# 07-POWER.net
KiCad netlist of a schematic drawn in Altium Designer
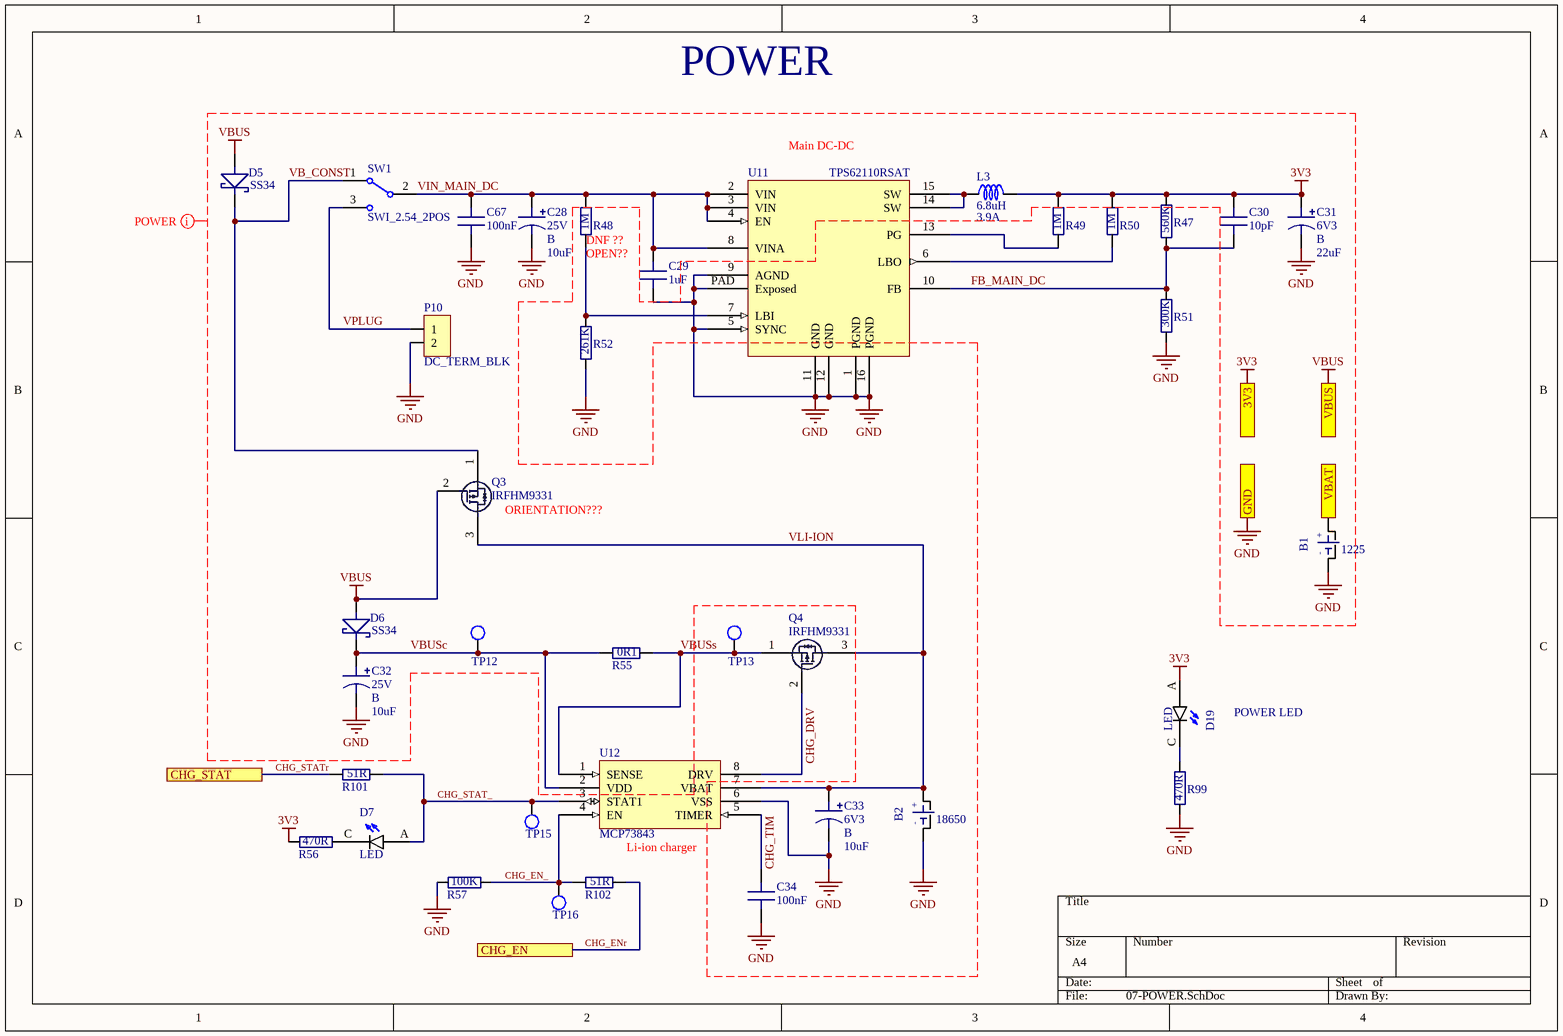
[diagram p0: 07-POWER.SchDoc]

(export (version "E")
  (design (tool "Eeschema 10.0.6"))
  (components
    (comp (ref "B1")
      (value "CR12XX_BH500")
      (footprint "BH500-CR1216/20/25-COMB")
      (description "Coin Cell Battery 3V 12 X 2.5 mm 48mA Holder")
      (fields
        (field (name "MP") "BR1225")
        (field (name "MF") "Panasonic Battery")
        (field (name "SIZE") "1225")
      )
      (libsource (lib "A.Shelestov_Batteries") (part "CR12XX_BH500"))
    )
    (comp (ref "B2")
      (value "18650_KEYS1042_HOLDER")
      (footprint "18650-COMBI")
      (description "18650 Li-ion Battery Holder")
      (fields (field (name "SIZE") "18650"))
      (libsource (lib "A.Shelestov_Batteries") (part "18650_KEYS1042_HOLDER"))
    )
    (comp (ref "C28")
      (value "10uF")
      (footprint "CAP_SIZE_B")
      (description "Tantalum capacitor")
      (fields (field (name "VOLTAGE") "25V") (field (name "SIZE") "B"))
      (libsource (lib "A.Shelestov_Capacitors") (part "CAP_B_10uF_25V"))
    )
    (comp (ref "C29")
      (value "1uF")
      (footprint "C0805")
      (description "Ceramic capacitor")
      (fields (field (name "VOLTAGE") "25V"))
      (libsource (lib "A.Shelestov_Capacitors") (part "C0805_1uF_25V"))
    )
    (comp (ref "C30")
      (value "10pF")
      (footprint "C0603")
      (description "Ceramic capacitor")
      (fields (field (name "VOLTAGE") "25V"))
      (libsource (lib "A.Shelestov_Capacitors") (part "C0603_10pF_25V"))
    )
    (comp (ref "C31")
      (value "22uF")
      (footprint "CAP_SIZE_B")
      (description "Tantalum capacitor")
      (fields (field (name "VOLTAGE") "6V3") (field (name "SIZE") "B"))
      (libsource (lib "A.Shelestov_Capacitors") (part "CAP_B_22uF_6V3"))
    )
    (comp (ref "C32")
      (value "10uF")
      (footprint "CAP_SIZE_B")
      (description "Tantalum capacitor")
      (fields (field (name "VOLTAGE") "25V") (field (name "SIZE") "B"))
      (libsource (lib "A.Shelestov_Capacitors") (part "CAP_B_10uF_25V"))
    )
    (comp (ref "C33")
      (value "10uF")
      (footprint "CAP_SIZE_B")
      (description "Tantalum capacitor")
      (fields (field (name "VOLTAGE") "6V3") (field (name "SIZE") "B"))
      (libsource (lib "A.Shelestov_Capacitors") (part "CAP_B_10uF_6V3"))
    )
    (comp (ref "C34")
      (value "100nF")
      (footprint "C0805")
      (description "Ceramic capacitor")
      (fields (field (name "VOLTAGE") "25V"))
      (libsource (lib "A.Shelestov_Capacitors") (part "C0805_100nF_25V"))
    )
    (comp (ref "C67")
      (value "100nF")
      (footprint "C0805")
      (description "Ceramic capacitor")
      (fields (field (name "VOLTAGE") "25V"))
      (libsource (lib "A.Shelestov_Capacitors") (part "C0805_100nF_25V"))
    )
    (comp (ref "D5")
      (value "SMD-DIODE-SCHOTTKY-40V-3A(DO-214AB)")
      (footprint "DO-214AC")
      (description "Rectifier, Schottky; DO-214AB; 3.0A IF; 0.75V; 40V; 100A IFRM; 10000V/us; 1000pF")
      (fields (field (name "MF") "Vishay") (field (name "MP") "SS34-E3/57T") (field (name "NAME") "SS34"))
      (libsource (lib "ComponentsLib") (part "D_SS-34"))
    )
    (comp (ref "D6")
      (value "SMD-DIODE-SCHOTTKY-40V-3A(DO-214AB)")
      (footprint "DO-214AC")
      (description "Rectifier, Schottky; DO-214AB; 3.0A IF; 0.75V; 40V; 100A IFRM; 10000V/us; 1000pF")
      (fields (field (name "MF") "Vishay") (field (name "MP") "SS34-E3/57T") (field (name "NAME") "SS34"))
      (libsource (lib "ComponentsLib") (part "D_SS-34"))
    )
    (comp (ref "D7")
      (value "LED")
      (footprint "LED_0604")
      (description "Led General")
      (fields (field (name "MF") "Dialight") (field (name "MP") "598-8140-107F"))
      (libsource (lib "ComponentsLib") (part "LED"))
    )
    (comp (ref "D19")
      (value "LED")
      (footprint "LED_0604")
      (description "Led General")
      (fields (field (name "MF") "Dialight") (field (name "MP") "598-8140-107F"))
      (libsource (lib "ComponentsLib") (part "LED"))
    )
    (comp (ref "L3")
      (value "*")
      (footprint "L_CDRH8D43")
      (description "Inductor Generic")
      (fields (field (name "CURRENT") "3.9A") (field (name "INDUCTIVITY") "6.8uH"))
      (libsource (lib "A.Shelestov_Inductors") (part "L_CDHR8D43_6.8uH_3.9A"))
    )
    (comp (ref "P10")
      (value "DC_TERM_BLK")
      (footprint "TERM_BLK_2.54")
      (libsource (lib "ComponentsLib") (part "DC_TERM_BLK"))
    )
    (comp (ref "Q3")
      (value "IRFHM9331")
      (footprint "PQFN-3x3")
      (description "-30V Single P-Channel HEXFET Power MOSFET in a PQFN 3mm x 3mm package")
      (libsource (lib "ComponentsLib") (part "IRFHM9331"))
    )
    (comp (ref "Q4")
      (value "IRFHM9331")
      (footprint "PQFN-3x3")
      (description "-30V Single P-Channel HEXFET Power MOSFET in a PQFN 3mm x 3mm package")
      (libsource (lib "ComponentsLib") (part "IRFHM9331"))
    )
    (comp (ref "R47")
      (value "~")
      (footprint "R0805")
      (description "Resistor General")
      (fields (field (name "TOLERANCE") "1%") (field (name "RESISTANCE") "560K"))
      (libsource (lib "A.Shelestov_Resistors") (part "R0805_560K_1%"))
    )
    (comp (ref "R48")
      (value "~")
      (footprint "R0805")
      (description "Resistor General")
      (fields (field (name "TOLERANCE") "1%") (field (name "RESISTANCE") "1M"))
      (libsource (lib "A.Shelestov_Resistors") (part "R0805_1M_1%"))
    )
    (comp (ref "R49")
      (value "~")
      (footprint "R0805")
      (description "Resistor General")
      (fields (field (name "TOLERANCE") "1%") (field (name "RESISTANCE") "1M"))
      (libsource (lib "A.Shelestov_Resistors") (part "R0805_1M_1%"))
    )
    (comp (ref "R50")
      (value "~")
      (footprint "R0805")
      (description "Resistor General")
      (fields (field (name "TOLERANCE") "1%") (field (name "RESISTANCE") "1M"))
      (libsource (lib "A.Shelestov_Resistors") (part "R0805_1M_1%"))
    )
    (comp (ref "R51")
      (value "~")
      (footprint "R0805")
      (description "Resistor General")
      (fields (field (name "TOLERANCE") "1%") (field (name "RESISTANCE") "300K"))
      (libsource (lib "A.Shelestov_Resistors") (part "R0805_300K_1%"))
    )
    (comp (ref "R52")
      (value "~")
      (footprint "R0805")
      (description "Resistor General")
      (fields (field (name "TOLERANCE") "1%") (field (name "RESISTANCE") "261K"))
      (libsource (lib "A.Shelestov_Resistors") (part "R0805_261K_1%"))
    )
    (comp (ref "R55")
      (value "~")
      (footprint "R2512")
      (description "Resistor General")
      (fields (field (name "TOLERANCE") "1%") (field (name "RESISTANCE") "0R1"))
      (libsource (lib "A.Shelestov_Resistors") (part "R2512_0R1_1%"))
    )
    (comp (ref "R56")
      (value "~")
      (footprint "R0603")
      (description "Resistor General")
      (fields (field (name "TOLERANCE") "5%") (field (name "RESISTANCE") "470R"))
      (libsource (lib "A.Shelestov_Resistors") (part "R0603_470R"))
    )
    (comp (ref "R57")
      (value "~")
      (footprint "R0603")
      (description "Resistor General")
      (fields (field (name "TOLERANCE") "5%") (field (name "RESISTANCE") "100K"))
      (libsource (lib "A.Shelestov_Resistors") (part "R0603_100K"))
    )
    (comp (ref "R99")
      (value "~")
      (footprint "R0603")
      (description "Resistor General")
      (fields (field (name "TOLERANCE") "5%") (field (name "RESISTANCE") "470R"))
      (libsource (lib "A.Shelestov_Resistors") (part "R0603_470R"))
    )
    (comp (ref "R101")
      (value "~")
      (footprint "R0402")
      (description "Resistor General")
      (fields (field (name "RESISTANCE") "51R"))
      (libsource (lib "A.Shelestov_Resistors") (part "R0402_51R"))
    )
    (comp (ref "R102")
      (value "~")
      (footprint "R0402")
      (description "Resistor General")
      (fields (field (name "RESISTANCE") "51R"))
      (libsource (lib "A.Shelestov_Resistors") (part "R0402_51R"))
    )
    (comp (ref "SW1")
      (value "SWI_2.54_2POS")
      (footprint "SW_1x3 2.54")
      (description "Generich 2 pos switch")
      (libsource (lib "ComponentsLib") (part "SWI_2.54_2POS"))
    )
    (comp (ref "TP12")
      (value "TEST_POINT")
      (footprint "TP_1mm")
      (libsource (lib "ComponentsLib") (part "TEST_POINT"))
    )
    (comp (ref "TP13")
      (value "TEST_POINT")
      (footprint "TP_1mm")
      (libsource (lib "ComponentsLib") (part "TEST_POINT"))
    )
    (comp (ref "TP15")
      (value "TEST_POINT")
      (footprint "TP_1mm")
      (libsource (lib "ComponentsLib") (part "TEST_POINT"))
    )
    (comp (ref "TP16")
      (value "TEST_POINT")
      (footprint "TP_1mm")
      (libsource (lib "ComponentsLib") (part "TEST_POINT"))
    )
    (comp (ref "U11")
      (value "TPS62110RSAT")
      (footprint "VQFN-16")
      (description "TPS6211x 17-V, 1.5-A, Synchronous Step-Down Converter")
      (libsource (lib "ComponentsLib") (part "TPS62110RSAT"))
    )
    (comp (ref "U12")
      (value "MCP73843")
      (footprint "MSOP-8-SOP65P490X110-8N")
      (description "MCP73843 Single Li-ion cell charger IC")
      (fields (field (name "MF") "Microchip"))
      (libsource (lib "ComponentsLib") (part "MCP73843"))
    )
  )
  (nets
    (net (code "1") (name "/CHG_DRV") (class "Default")
      (node (ref "Q4") (pin "2") (pinfunction "G_2") (pintype "passive"))
      (node (ref "U12") (pin "8") (pinfunction "DRV_8") (pintype "power_in"))
    )
    (net (code "2") (name "/CHG_EN_") (class "Default")
      (node (ref "R102") (pin "1") (pinfunction "1_1") (pintype "passive"))
      (node (ref "R57") (pin "2") (pinfunction "2_2") (pintype "passive"))
      (node (ref "TP16") (pin "1") (pinfunction "1_1") (pintype "passive"))
      (node (ref "U12") (pin "4") (pinfunction "EN_4") (pintype "input"))
    )
    (net (code "3") (name "/CHG_ENr") (class "Default")
      (node (ref "R102") (pin "2") (pinfunction "2_2") (pintype "passive"))
    )
    (net (code "4") (name "/CHG_STAT_") (class "Default")
      (node (ref "D7") (pin "A") (pinfunction "A_A") (pintype "passive"))
      (node (ref "R101") (pin "2") (pinfunction "2_2") (pintype "passive"))
      (node (ref "TP15") (pin "1") (pinfunction "1_1") (pintype "passive"))
      (node (ref "U12") (pin "3") (pinfunction "STAT1_3") (pintype "bidirectional"))
    )
    (net (code "5") (name "/CHG_STATr") (class "Default")
      (node (ref "R101") (pin "1") (pinfunction "1_1") (pintype "passive"))
    )
    (net (code "6") (name "/CHG_TIM") (class "Default")
      (node (ref "C34") (pin "2") (pinfunction "2_2") (pintype "passive"))
      (node (ref "U12") (pin "5") (pinfunction "TIMER_5") (pintype "input"))
    )
    (net (code "7") (name "/FB_MAIN_DC") (class "Default")
      (node (ref "C30") (pin "2") (pinfunction "2_2") (pintype "passive"))
      (node (ref "R47") (pin "1") (pinfunction "1_1") (pintype "passive"))
      (node (ref "R51") (pin "2") (pinfunction "2_2") (pintype "passive"))
      (node (ref "U11") (pin "10") (pinfunction "FB_10") (pintype "power_in"))
    )
    (net (code "8") (name "/VBAT") (class "Default")
      (node (ref "B1") (pin "POS") (pinfunction "POS_POS") (pintype "passive"))
    )
    (net (code "9") (name "/VBUSc") (class "Default")
      (node (ref "C32") (pin "1") (pinfunction "1_1") (pintype "passive"))
      (node (ref "D6") (pin "C") (pinfunction "NEG_C") (pintype "passive"))
      (node (ref "R55") (pin "1") (pinfunction "1_1") (pintype "passive"))
      (node (ref "TP12") (pin "1") (pinfunction "1_1") (pintype "passive"))
      (node (ref "U12") (pin "2") (pinfunction "VDD_2") (pintype "power_in"))
    )
    (net (code "10") (name "/VBUSs") (class "Default")
      (node (ref "Q4") (pin "1") (pinfunction "S_1") (pintype "passive"))
      (node (ref "R55") (pin "2") (pinfunction "2_2") (pintype "passive"))
      (node (ref "TP13") (pin "1") (pinfunction "1_1") (pintype "passive"))
      (node (ref "U12") (pin "1") (pinfunction "SENSE_1") (pintype "input"))
    )
    (net (code "11") (name "/VB_CONST") (class "Default")
      (node (ref "D5") (pin "C") (pinfunction "NEG_C") (pintype "passive"))
      (node (ref "Q3") (pin "1") (pinfunction "S_1") (pintype "passive"))
      (node (ref "SW1") (pin "1") (pinfunction "1_1") (pintype "passive"))
    )
    (net (code "12") (name "/VIN_MAIN_DC") (class "Default")
      (node (ref "C28") (pin "1") (pinfunction "1_1") (pintype "passive"))
      (node (ref "C29") (pin "2") (pinfunction "2_2") (pintype "passive"))
      (node (ref "C67") (pin "2") (pinfunction "2_2") (pintype "passive"))
      (node (ref "R48") (pin "2") (pinfunction "2_2") (pintype "passive"))
      (node (ref "SW1") (pin "2") (pinfunction "2_2") (pintype "passive"))
      (node (ref "U11") (pin "2") (pinfunction "VIN_2") (pintype "power_in"))
      (node (ref "U11") (pin "3") (pinfunction "VIN_3") (pintype "power_in"))
      (node (ref "U11") (pin "4") (pinfunction "EN_4") (pintype "input"))
      (node (ref "U11") (pin "8") (pinfunction "VINA_8") (pintype "power_in"))
    )
    (net (code "13") (name "/VLI-ION") (class "Default")
      (node (ref "B2") (pin "POS") (pinfunction "POS_POS") (pintype "passive"))
      (node (ref "C33") (pin "1") (pinfunction "1_1") (pintype "passive"))
      (node (ref "Q3") (pin "3") (pinfunction "D_3") (pintype "passive"))
      (node (ref "Q4") (pin "3") (pinfunction "D_3") (pintype "passive"))
      (node (ref "U12") (pin "7") (pinfunction "VBAT_7") (pintype "power_in"))
    )
    (net (code "14") (name "/VPLUG") (class "Default")
      (node (ref "P10") (pin "1") (pinfunction "1_1") (pintype "passive"))
      (node (ref "SW1") (pin "3") (pinfunction "3_3") (pintype "passive"))
    )
    (net (code "15") (name "3V3") (class "Default")
      (node (ref "C30") (pin "1") (pinfunction "1_1") (pintype "passive"))
      (node (ref "C31") (pin "1") (pinfunction "1_1") (pintype "passive"))
      (node (ref "D19") (pin "A") (pinfunction "A_A") (pintype "passive"))
      (node (ref "L3") (pin "2") (pinfunction "2_2") (pintype "passive"))
      (node (ref "R47") (pin "2") (pinfunction "2_2") (pintype "passive"))
      (node (ref "R49") (pin "2") (pinfunction "2_2") (pintype "passive"))
      (node (ref "R50") (pin "2") (pinfunction "2_2") (pintype "passive"))
      (node (ref "R56") (pin "1") (pinfunction "1_1") (pintype "passive"))
    )
    (net (code "16") (name "GND") (class "Default")
      (node (ref "B1") (pin "NEG") (pinfunction "NEG_NEG") (pintype "passive"))
      (node (ref "B2") (pin "NEG") (pinfunction "NEG_NEG") (pintype "passive"))
      (node (ref "C28") (pin "2") (pinfunction "2_2") (pintype "passive"))
      (node (ref "C29") (pin "1") (pinfunction "1_1") (pintype "passive"))
      (node (ref "C31") (pin "2") (pinfunction "2_2") (pintype "passive"))
      (node (ref "C32") (pin "2") (pinfunction "2_2") (pintype "passive"))
      (node (ref "C33") (pin "2") (pinfunction "2_2") (pintype "passive"))
      (node (ref "C34") (pin "1") (pinfunction "1_1") (pintype "passive"))
      (node (ref "C67") (pin "1") (pinfunction "1_1") (pintype "passive"))
      (node (ref "P10") (pin "2") (pinfunction "2_2") (pintype "passive"))
      (node (ref "R51") (pin "1") (pinfunction "1_1") (pintype "passive"))
      (node (ref "R52") (pin "1") (pinfunction "1_1") (pintype "passive"))
      (node (ref "R57") (pin "1") (pinfunction "1_1") (pintype "passive"))
      (node (ref "R99") (pin "1") (pinfunction "1_1") (pintype "passive"))
      (node (ref "U11") (pin "1") (pinfunction "PGND_1") (pintype "power_in"))
      (node (ref "U11") (pin "11") (pinfunction "GND_11") (pintype "power_in"))
      (node (ref "U11") (pin "12") (pinfunction "GND_12") (pintype "power_in"))
      (node (ref "U11") (pin "16") (pinfunction "PGND_16") (pintype "power_in"))
      (node (ref "U11") (pin "5") (pinfunction "SYNC_5") (pintype "input"))
      (node (ref "U11") (pin "9") (pinfunction "AGND_9") (pintype "power_in"))
      (node (ref "U11") (pin "PAD") (pinfunction "Exposed_PAD") (pintype "power_in"))
      (node (ref "U12") (pin "6") (pinfunction "VSS_6") (pintype "power_in"))
    )
    (net (code "17") (name "Net-(D7-PadC)") (class "Default")
      (node (ref "D7") (pin "C") (pinfunction "C_C") (pintype "passive"))
      (node (ref "R56") (pin "2") (pinfunction "2_2") (pintype "passive"))
    )
    (net (code "18") (name "Net-(D19-PadC)") (class "Default")
      (node (ref "D19") (pin "C") (pinfunction "C_C") (pintype "passive"))
      (node (ref "R99") (pin "2") (pinfunction "2_2") (pintype "passive"))
    )
    (net (code "19") (name "Net-(L3-Pad1)") (class "Default")
      (node (ref "L3") (pin "1") (pinfunction "1_1") (pintype "passive"))
      (node (ref "U11") (pin "14") (pinfunction "SW_14") (pintype "power_in"))
      (node (ref "U11") (pin "15") (pinfunction "SW_15") (pintype "power_in"))
    )
    (net (code "20") (name "Net-(U11-LBI)") (class "Default")
      (node (ref "R48") (pin "1") (pinfunction "1_1") (pintype "passive"))
      (node (ref "R52") (pin "2") (pinfunction "2_2") (pintype "passive"))
      (node (ref "U11") (pin "7") (pinfunction "LBI_7") (pintype "input"))
    )
    (net (code "21") (name "Net-(U11-LBO)") (class "Default")
      (node (ref "R50") (pin "1") (pinfunction "1_1") (pintype "passive"))
      (node (ref "U11") (pin "6") (pinfunction "LBO_6") (pintype "output"))
    )
    (net (code "22") (name "Net-(U11-PG)") (class "Default")
      (node (ref "R49") (pin "1") (pinfunction "1_1") (pintype "passive"))
      (node (ref "U11") (pin "13") (pinfunction "PG_13") (pintype "power_in"))
    )
    (net (code "23") (name "VBUS") (class "Default")
      (node (ref "D5") (pin "A") (pinfunction "POS_A") (pintype "passive"))
      (node (ref "D6") (pin "A") (pinfunction "POS_A") (pintype "passive"))
      (node (ref "Q3") (pin "2") (pinfunction "G_2") (pintype "passive"))
    )
  )
)
